# Robot_demoborad.net
KiCad netlist of a schematic drawn in Altium Designer
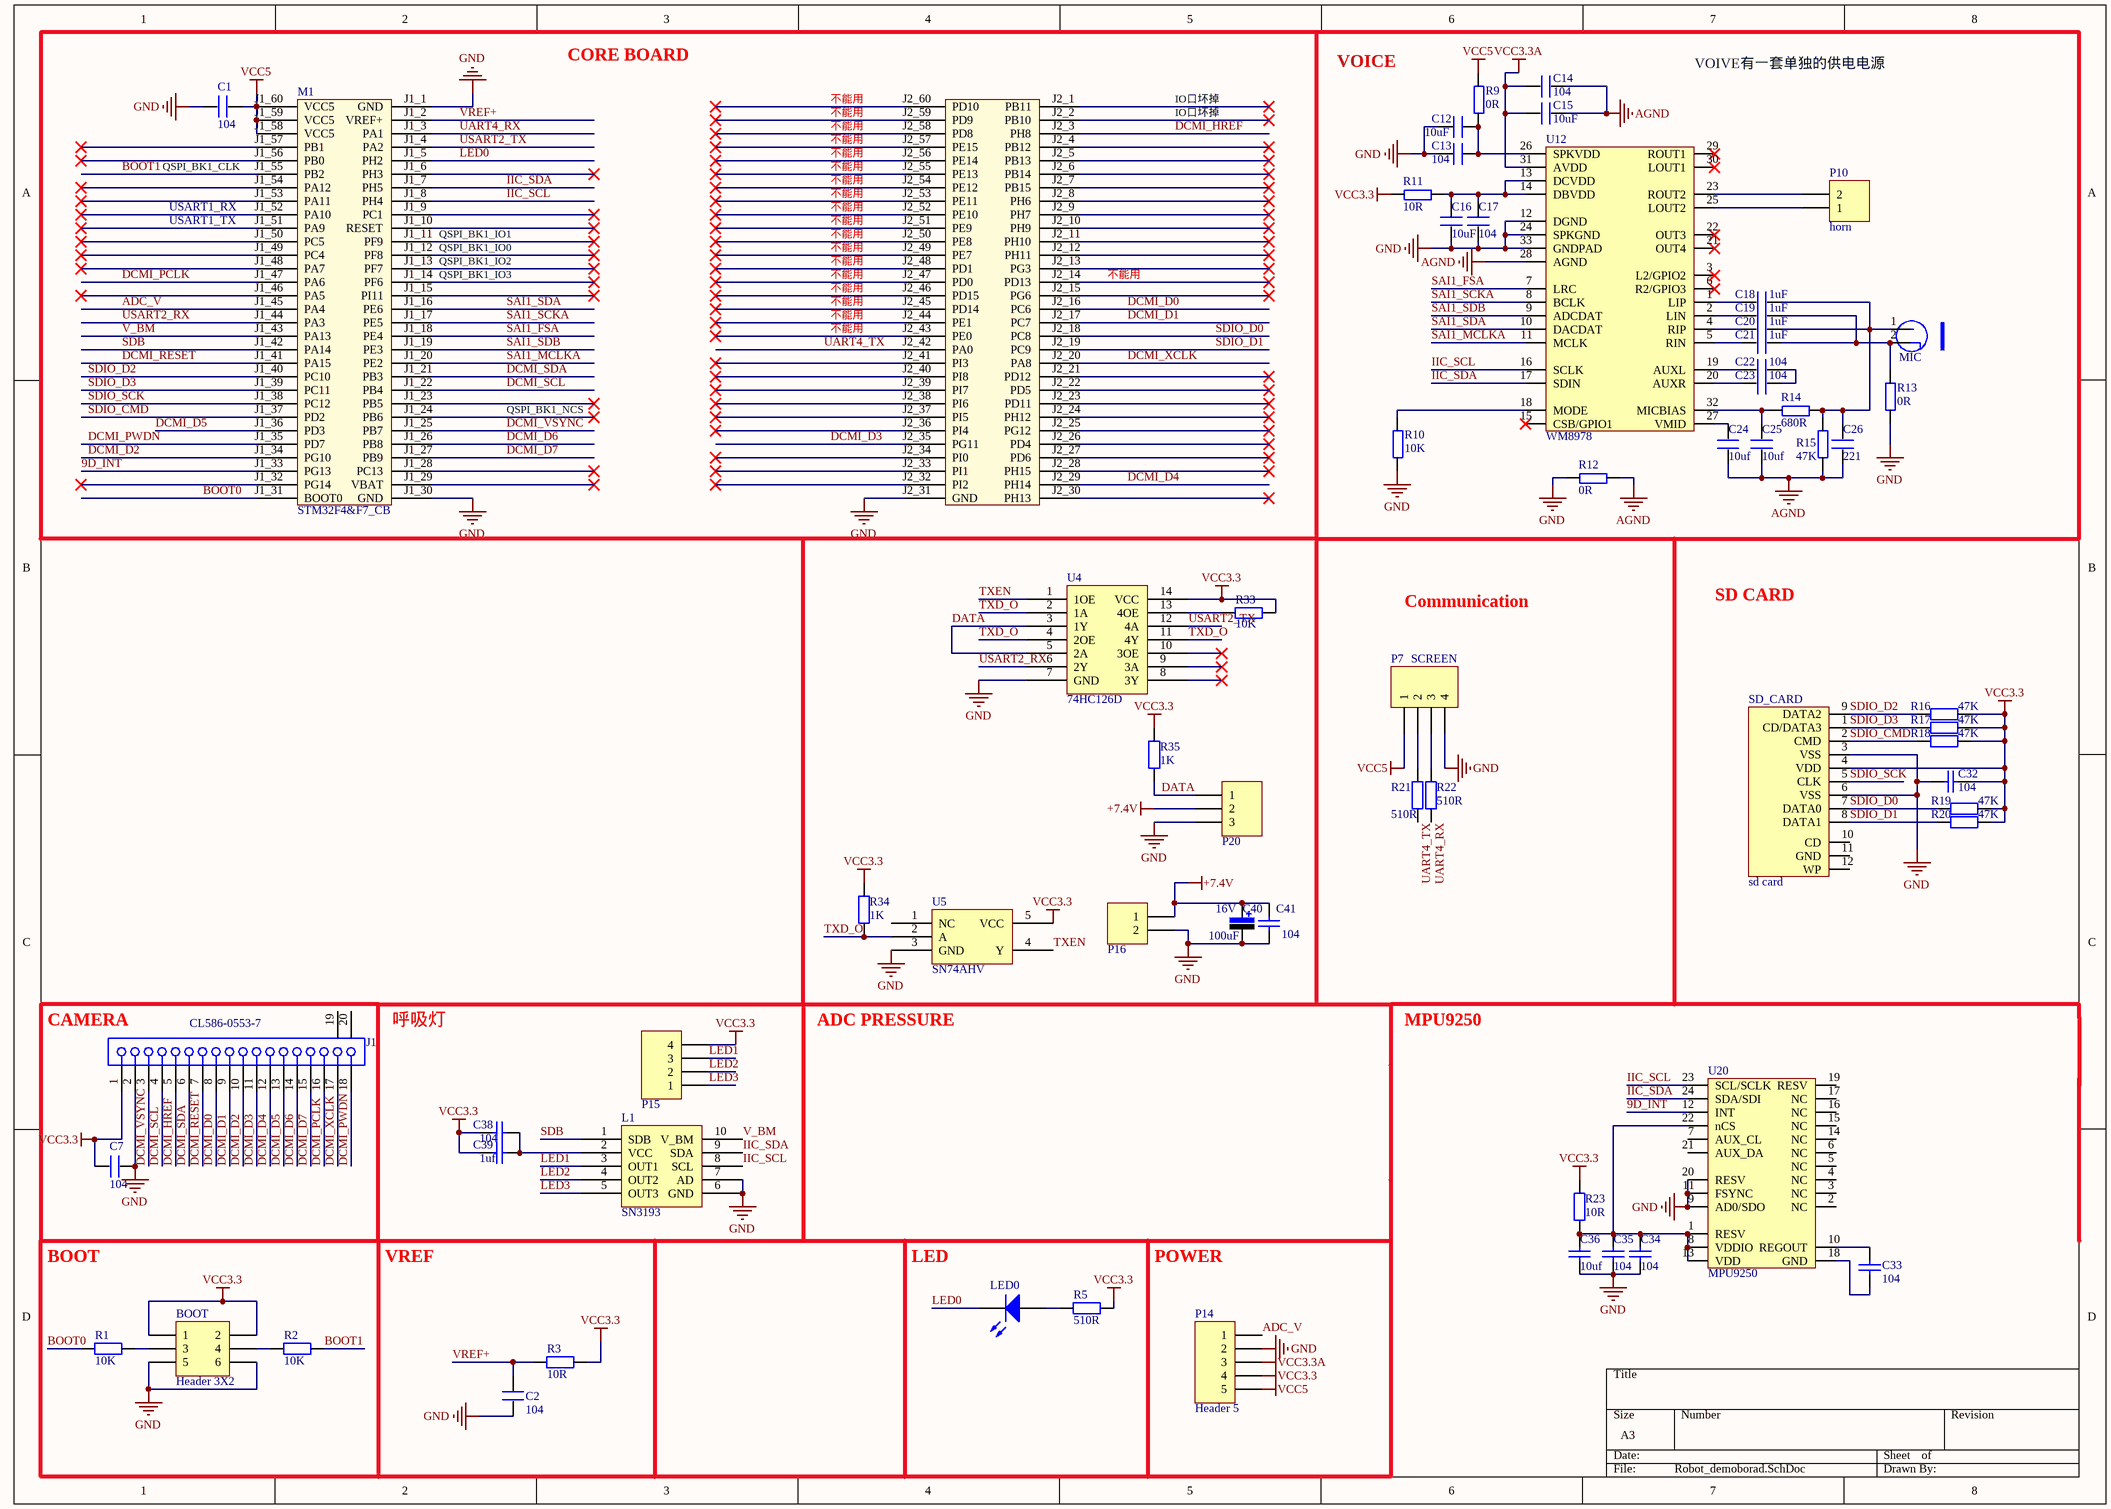
[diagram p0: Robot_demoborad.SchDoc]

(export (version "E")
  (design (tool "Eeschema 10.0.6"))
  (components
    (comp (ref "BOOT")
      (value "Header 3X2")
      (footprint "HDR2X3")
      (description "Header, 3-Pin, Dual row")
      (fields (field (name "PUBLISHER") "Altium Limited"))
      (libsource (lib "阿波罗STM32F4&F7底板封装库") (part "Header 3X2"))
    )
    (comp (ref "C1") (value "104") (footprint "0805") (libsource (lib "阿波罗STM32F4&F7底板封装库") (part "C")))
    (comp (ref "C2") (value "104") (footprint "0805") (libsource (lib "阿波罗STM32F4&F7底板封装库") (part "C")))
    (comp (ref "C7") (value "104") (footprint "0805") (libsource (lib "阿波罗STM32F4&F7底板封装库") (part "C")))
    (comp (ref "C12") (value "10uF") (footprint "0603P") (libsource (lib "阿波罗STM32F4&F7底板封装库") (part "C")))
    (comp (ref "C13") (value "104") (footprint "0603P") (libsource (lib "阿波罗STM32F4&F7底板封装库") (part "C")))
    (comp (ref "C14") (value "104") (footprint "0603P") (libsource (lib "阿波罗STM32F4&F7底板封装库") (part "C")))
    (comp (ref "C15") (value "10uF") (footprint "0603P") (libsource (lib "阿波罗STM32F4&F7底板封装库") (part "C")))
    (comp (ref "C16") (value "10uF") (footprint "0603P") (libsource (lib "阿波罗STM32F4&F7底板封装库") (part "C")))
    (comp (ref "C17") (value "104") (footprint "0603P") (libsource (lib "阿波罗STM32F4&F7底板封装库") (part "C")))
    (comp (ref "C18") (value "1uF") (footprint "0603P") (libsource (lib "阿波罗STM32F4&F7底板封装库") (part "C")))
    (comp (ref "C19") (value "1uF") (footprint "0603P") (libsource (lib "阿波罗STM32F4&F7底板封装库") (part "C")))
    (comp (ref "C20") (value "1uF") (footprint "0603P") (libsource (lib "阿波罗STM32F4&F7底板封装库") (part "C")))
    (comp (ref "C21") (value "1uF") (footprint "0603P") (libsource (lib "阿波罗STM32F4&F7底板封装库") (part "C")))
    (comp (ref "C22") (value "104") (footprint "0603P") (libsource (lib "阿波罗STM32F4&F7底板封装库") (part "C")))
    (comp (ref "C23") (value "104") (footprint "0603P") (libsource (lib "阿波罗STM32F4&F7底板封装库") (part "C")))
    (comp (ref "C24") (value "10uf") (footprint "0603P") (libsource (lib "阿波罗STM32F4&F7底板封装库") (part "C")))
    (comp (ref "C25") (value "10uf") (footprint "0603P") (libsource (lib "阿波罗STM32F4&F7底板封装库") (part "C")))
    (comp (ref "C26") (value "221") (footprint "0603P") (libsource (lib "阿波罗STM32F4&F7底板封装库") (part "C")))
    (comp (ref "C32")
      (value "104")
      (footprint "C-RAD-0805")
      (description "无极性电容")
      (fields (field (name "Comment") "Cap") (field (name "PUBLISHER") "Altium Limited"))
      (libsource (lib "Fszhang") (part "Cap"))
    )
    (comp (ref "C33")
      (value "104")
      (footprint "0603P")
      (description "无极性电容")
      (fields (field (name "Comment") "Cap") (field (name "PUBLISHER") "Altium Limited"))
      (libsource (lib "Fszhang") (part "Cap"))
    )
    (comp (ref "C34")
      (value "104")
      (footprint "0603P")
      (description "无极性电容")
      (fields (field (name "Comment") "Cap") (field (name "PUBLISHER") "Altium Limited"))
      (libsource (lib "Fszhang") (part "Cap"))
    )
    (comp (ref "C35")
      (value "104")
      (footprint "0603P")
      (description "无极性电容")
      (fields (field (name "Comment") "Cap") (field (name "PUBLISHER") "Altium Limited"))
      (libsource (lib "Fszhang") (part "Cap"))
    )
    (comp (ref "C36")
      (value "10uf")
      (footprint "0603P")
      (description "无极性电容")
      (fields (field (name "Comment") "Cap") (field (name "PUBLISHER") "Altium Limited"))
      (libsource (lib "Fszhang") (part "Cap"))
    )
    (comp (ref "C38")
      (value "104")
      (footprint "C-RAD-0805")
      (description "无极性电容")
      (fields (field (name "Comment") "Cap") (field (name "PUBLISHER") "Altium Limited"))
      (libsource (lib "Fszhang") (part "Cap"))
    )
    (comp (ref "C39")
      (value "1uf")
      (footprint "C-RAD-0805")
      (description "无极性电容")
      (fields (field (name "Comment") "Cap") (field (name "PUBLISHER") "Altium Limited"))
      (libsource (lib "Fszhang") (part "Cap"))
    )
    (comp (ref "C40")
      (value "100uF")
      (footprint "C-RB-8")
      (description "极性电解电容")
      (fields
        (field (name "VOL") "16V")
        (field (name "Comment") "Cap Pol")
        (field (name "PUBLISHER") "Altium Limited")
      )
      (libsource (lib "Fszhang") (part "Cap Pol"))
    )
    (comp (ref "C41")
      (value "104")
      (footprint "C-RAD-0805")
      (description "无极性电容")
      (fields (field (name "Comment") "Cap") (field (name "PUBLISHER") "Altium Limited"))
      (libsource (lib "Fszhang") (part "Cap"))
    )
    (comp (ref "J1")
      (value "CL586-0553-7")
      (footprint "FH12A-18S-0.5SH")
      (description "FH12 Series, \"Flip-Lock\" SMT/ZIF Connector - 0.5mm Spaced Top Contact")
      (fields (field (name "PUBLISHER") "Altium Limited"))
      (libsource (lib "HRS FPC-FFC FH12 Series") (part "CL586-0553-7"))
    )
    (comp (ref "L1") (value "SN3193") (footprint "DFN_10") (libsource (lib "SN393") (part "Component_1")))
    (comp (ref "LED0")
      (value "LED1")
      (footprint "6-0805_M")
      (description "Typical RED, GREEN, YELLOW, AMBER GaAs LED")
      (fields (field (name "PUBLISHER") "Altium Limited"))
      (libsource (lib "阿波罗STM32F4&F7底板封装库") (part "LED2"))
    )
    (comp (ref "M1")
      (value "STM32F4&F7_CB")
      (footprint "STM32F4&F7_CB")
      (description "F429/746 Core Board")
      (libsource (lib "阿波罗STM32F4&F7底板封装库") (part "STM32F4&F7_CB"))
    )
    (comp (ref "MIC1")
      (value "MIC")
      (footprint "HDR2X1_B1")
      (libsource (lib "阿波罗STM32F4&F7底板封装库") (part "MIC"))
    )
    (comp (ref "P7")
      (value "SCREEN")
      (footprint "HDR1X4H")
      (description "Header, 4-Pin, Right Angle")
      (fields (field (name "PUBLISHER") "Altium Limited"))
      (libsource (lib "Miscellaneous Connectors") (part "Header 4H"))
    )
    (comp (ref "P10")
      (value "horn")
      (footprint "HDR1X2H")
      (description "Header, 2-Pin, Right Angle")
      (fields (field (name "PUBLISHER") "Altium Limited"))
      (libsource (lib "Miscellaneous Connectors") (part "Header 2H"))
    )
    (comp (ref "P14")
      (value "Header 5")
      (footprint "HDR1X5H")
      (description "Header, 5-Pin")
      (fields (field (name "PUBLISHER") "Altium Limited"))
      (libsource (lib "Miscellaneous Connectors") (part "Header 5"))
    )
    (comp (ref "P15")
      (value "Header 4")
      (footprint "HDR4X1_B2")
      (description "接插件")
      (fields (field (name "PUBLISHER") "Altium Limited"))
      (libsource (lib "Fszhang") (part "Header 4"))
    )
    (comp (ref "P16")
      (value "Header 2")
      (footprint "HDR2X1_B2")
      (description "接插件")
      (fields (field (name "PUBLISHER") "Altium Limited"))
      (libsource (lib "Fszhang") (part "Header 2"))
    )
    (comp (ref "P20")
      (value "Header 3")
      (footprint "HDR3X1_B1")
      (description "接插件")
      (fields (field (name "PUBLISHER") "Altium Limited"))
      (libsource (lib "Fszhang") (part "Header 3"))
    )
    (comp (ref "R1")
      (value "10K")
      (footprint "6-0805_N")
      (description "Resistor")
      (fields (field (name "Comment") "Res2") (field (name "PUBLISHER") "Altium Limited"))
      (libsource (lib "Miscellaneous Devices") (part "Res2"))
    )
    (comp (ref "R2")
      (value "10K")
      (footprint "6-0805_N")
      (description "Resistor")
      (fields (field (name "Comment") "Res2") (field (name "PUBLISHER") "Altium Limited"))
      (libsource (lib "Miscellaneous Devices") (part "Res2"))
    )
    (comp (ref "R3")
      (value "10R")
      (footprint "6-0805_N")
      (description "Resistor")
      (fields (field (name "Comment") "Res2") (field (name "PUBLISHER") "Altium Limited"))
      (libsource (lib "Miscellaneous Devices") (part "Res2"))
    )
    (comp (ref "R5")
      (value "510R")
      (footprint "6-0805_N")
      (description "Resistor")
      (fields (field (name "Comment") "Res2") (field (name "PUBLISHER") "Altium Limited"))
      (libsource (lib "Miscellaneous Devices") (part "Res2"))
    )
    (comp (ref "R9") (value "0R") (footprint "0603P") (libsource (lib "阿波罗STM32F4&F7底板封装库") (part "R")))
    (comp (ref "R10") (value "10K") (footprint "0603P") (libsource (lib "阿波罗STM32F4&F7底板封装库") (part "R")))
    (comp (ref "R11") (value "10R") (footprint "0603P") (libsource (lib "阿波罗STM32F4&F7底板封装库") (part "R")))
    (comp (ref "R12") (value "0R") (footprint "0603P") (libsource (lib "阿波罗STM32F4&F7底板封装库") (part "R")))
    (comp (ref "R13") (value "0R") (footprint "0603P") (libsource (lib "阿波罗STM32F4&F7底板封装库") (part "R")))
    (comp (ref "R14") (value "680R") (footprint "0603P") (libsource (lib "阿波罗STM32F4&F7底板封装库") (part "R")))
    (comp (ref "R15") (value "47K") (footprint "0603P") (libsource (lib "阿波罗STM32F4&F7底板封装库") (part "R")))
    (comp (ref "R16")
      (value "47K")
      (footprint "0805-1")
      (description "贴片电阻")
      (fields (field (name "Comment") "Res1") (field (name "PUBLISHER") "Altium Limited"))
      (libsource (lib "") (part "Res1_1"))
    )
    (comp (ref "R17")
      (value "47K")
      (footprint "0805-1")
      (description "贴片电阻")
      (fields (field (name "Comment") "Res1") (field (name "PUBLISHER") "Altium Limited"))
      (libsource (lib "") (part "Res1_1"))
    )
    (comp (ref "R18")
      (value "47K")
      (footprint "0805-1")
      (description "贴片电阻")
      (fields (field (name "Comment") "Res1") (field (name "PUBLISHER") "Altium Limited"))
      (libsource (lib "") (part "Res1_1"))
    )
    (comp (ref "R19")
      (value "47K")
      (footprint "0805-1")
      (description "贴片电阻")
      (fields (field (name "Comment") "Res1") (field (name "PUBLISHER") "Altium Limited"))
      (libsource (lib "") (part "Res1_1"))
    )
    (comp (ref "R20")
      (value "47K")
      (footprint "0805-1")
      (description "贴片电阻")
      (fields (field (name "Comment") "Res1") (field (name "PUBLISHER") "Altium Limited"))
      (libsource (lib "") (part "Res1_1"))
    )
    (comp (ref "R21")
      (value "510R")
      (footprint "0805-1")
      (description "贴片电阻")
      (fields (field (name "Comment") "Res1") (field (name "PUBLISHER") "Altium Limited"))
      (libsource (lib "Fszhang") (part "Res1"))
    )
    (comp (ref "R22")
      (value "510R")
      (footprint "0805-1")
      (description "贴片电阻")
      (fields (field (name "Comment") "Res1") (field (name "PUBLISHER") "Altium Limited"))
      (libsource (lib "Fszhang") (part "Res1"))
    )
    (comp (ref "R23")
      (value "10R")
      (footprint "0603P")
      (description "贴片电阻")
      (fields (field (name "Comment") "Res1") (field (name "PUBLISHER") "Altium Limited"))
      (libsource (lib "Fszhang") (part "Res1"))
    )
    (comp (ref "R33")
      (value "10K")
      (footprint "0805-1")
      (description "贴片电阻")
      (fields (field (name "Comment") "Res1") (field (name "PUBLISHER") "Altium Limited"))
      (libsource (lib "") (part "Res1_1"))
    )
    (comp (ref "R34")
      (value "1K")
      (footprint "0805-1")
      (description "贴片电阻")
      (fields (field (name "Comment") "Res1") (field (name "PUBLISHER") "Altium Limited"))
      (libsource (lib "Fszhang") (part "Res1"))
    )
    (comp (ref "R35")
      (value "1K")
      (footprint "0805-1")
      (description "贴片电阻")
      (fields (field (name "Comment") "Res1") (field (name "PUBLISHER") "Altium Limited"))
      (libsource (lib "Fszhang") (part "Res1"))
    )
    (comp (ref "SD_CARD")
      (value "sd card")
      (footprint "SDCARD_L")
      (libsource (lib "阿波罗STM32F4&F7底板封装库") (part "sd card"))
    )
    (comp (ref "U4")
      (value "74HC126D")
      (footprint "SOP-14N")
      (libsource (lib "74HC126D") (part "Component_1"))
    )
    (comp (ref "U5")
      (value "SN74AHV")
      (footprint "SOT-23-5")
      (libsource (lib "SN74AHV") (part "Component_1"))
    )
    (comp (ref "U12")
      (value "WM8978")
      (footprint "qfn32")
      (description "24bit ADC&DAC")
      (libsource (lib "阿波罗STM32F4&F7底板封装库") (part "WM8978"))
    )
    (comp (ref "U20")
      (value "MPU9250")
      (footprint "QFN24-t")
      (description "9轴运动处理传感器")
      (libsource (lib "阿波罗STM32F4&F7底板封装库") (part "MPU9250"))
    )
  )
  (nets
    (net (code "1") (name "+7.4V") (class "Default")
      (node (ref "C40") (pin "1") (pinfunction "1_1") (pintype "passive"))
      (node (ref "C41") (pin "2") (pinfunction "2_2") (pintype "passive"))
      (node (ref "P16") (pin "1") (pinfunction "1_1") (pintype "passive"))
      (node (ref "P20") (pin "2") (pinfunction "2_2") (pintype "passive"))
    )
    (net (code "2") (name "/9D_INT") (class "Default")
      (node (ref "M1") (pin "J1_33") (pinfunction "PG13_J1_33") (pintype "passive"))
      (node (ref "U20") (pin "12") (pinfunction "INT_12") (pintype "passive"))
    )
    (net (code "3") (name "/ADC_V") (class "Default")
      (node (ref "M1") (pin "J1_45") (pinfunction "PA4_J1_45") (pintype "passive"))
      (node (ref "P14") (pin "1") (pinfunction "1_1") (pintype "passive"))
    )
    (net (code "4") (name "/BOOT0") (class "Default")
      (node (ref "M1") (pin "J1_31") (pinfunction "BOOT0_J1_31") (pintype "passive"))
      (node (ref "R1") (pin "1") (pinfunction "1_1") (pintype "passive"))
    )
    (net (code "5") (name "/BOOT1") (class "Default")
      (node (ref "M1") (pin "J1_55") (pinfunction "PB2_J1_55") (pintype "passive"))
      (node (ref "R2") (pin "2") (pinfunction "2_2") (pintype "passive"))
    )
    (net (code "6") (name "/DATA") (class "Default")
      (node (ref "P20") (pin "1") (pinfunction "1_1") (pintype "passive"))
      (node (ref "R35") (pin "1") (pinfunction "1_1") (pintype "passive"))
      (node (ref "U4") (pin "3") (pinfunction "1Y_3") (pintype "passive"))
      (node (ref "U4") (pin "5") (pinfunction "2A_5") (pintype "passive"))
    )
    (net (code "7") (name "/DCMI_D0") (class "Default")
      (node (ref "J1") (pin "8") (pinfunction "8_8") (pintype "passive"))
      (node (ref "M1") (pin "J2_16") (pinfunction "PC6_J2_16") (pintype "passive"))
    )
    (net (code "8") (name "/DCMI_D1") (class "Default")
      (node (ref "J1") (pin "9") (pinfunction "9_9") (pintype "passive"))
      (node (ref "M1") (pin "J2_17") (pinfunction "PC7_J2_17") (pintype "passive"))
    )
    (net (code "9") (name "/DCMI_D2") (class "Default")
      (node (ref "J1") (pin "10") (pinfunction "10_10") (pintype "passive"))
      (node (ref "M1") (pin "J1_34") (pinfunction "PG10_J1_34") (pintype "passive"))
    )
    (net (code "10") (name "/DCMI_D3") (class "Default")
      (node (ref "J1") (pin "11") (pinfunction "11_11") (pintype "passive"))
      (node (ref "M1") (pin "J2_35") (pinfunction "PG11_J2_35") (pintype "passive"))
    )
    (net (code "11") (name "/DCMI_D4") (class "Default")
      (node (ref "J1") (pin "12") (pinfunction "12_12") (pintype "passive"))
      (node (ref "M1") (pin "J2_29") (pinfunction "PH14_J2_29") (pintype "passive"))
    )
    (net (code "12") (name "/DCMI_D5") (class "Default")
      (node (ref "J1") (pin "13") (pinfunction "13_13") (pintype "passive"))
      (node (ref "M1") (pin "J1_36") (pinfunction "PD3_J1_36") (pintype "passive"))
    )
    (net (code "13") (name "/DCMI_D6") (class "Default")
      (node (ref "J1") (pin "14") (pinfunction "14_14") (pintype "passive"))
      (node (ref "M1") (pin "J1_26") (pinfunction "PB8_J1_26") (pintype "passive"))
    )
    (net (code "14") (name "/DCMI_D7") (class "Default")
      (node (ref "J1") (pin "15") (pinfunction "15_15") (pintype "passive"))
      (node (ref "M1") (pin "J1_27") (pinfunction "PB9_J1_27") (pintype "passive"))
    )
    (net (code "15") (name "/DCMI_HREF") (class "Default")
      (node (ref "J1") (pin "5") (pinfunction "5_5") (pintype "passive"))
      (node (ref "M1") (pin "J2_3") (pinfunction "PH8_J2_3") (pintype "passive"))
    )
    (net (code "16") (name "/DCMI_PCLK") (class "Default")
      (node (ref "J1") (pin "16") (pinfunction "16_16") (pintype "passive"))
      (node (ref "M1") (pin "J1_47") (pinfunction "PA6_J1_47") (pintype "passive"))
    )
    (net (code "17") (name "/DCMI_PWDN") (class "Default")
      (node (ref "J1") (pin "18") (pinfunction "18_18") (pintype "passive"))
      (node (ref "M1") (pin "J1_35") (pinfunction "PD7_J1_35") (pintype "passive"))
    )
    (net (code "18") (name "/DCMI_RESET") (class "Default")
      (node (ref "J1") (pin "7") (pinfunction "7_7") (pintype "passive"))
      (node (ref "M1") (pin "J1_41") (pinfunction "PA15_J1_41") (pintype "passive"))
    )
    (net (code "19") (name "/DCMI_SCL") (class "Default")
      (node (ref "J1") (pin "4") (pinfunction "4_4") (pintype "passive"))
      (node (ref "M1") (pin "J1_22") (pinfunction "PB4_J1_22") (pintype "passive"))
    )
    (net (code "20") (name "/DCMI_SDA") (class "Default")
      (node (ref "J1") (pin "6") (pinfunction "6_6") (pintype "passive"))
      (node (ref "M1") (pin "J1_21") (pinfunction "PB3_J1_21") (pintype "passive"))
    )
    (net (code "21") (name "/DCMI_VSYNC") (class "Default")
      (node (ref "J1") (pin "3") (pinfunction "3_3") (pintype "passive"))
      (node (ref "M1") (pin "J1_25") (pinfunction "PB7_J1_25") (pintype "passive"))
    )
    (net (code "22") (name "/DCMI_XCLK") (class "Default")
      (node (ref "J1") (pin "17") (pinfunction "17_17") (pintype "passive"))
      (node (ref "M1") (pin "J2_20") (pinfunction "PA8_J2_20") (pintype "passive"))
    )
    (net (code "23") (name "/IIC_SCL") (class "Default")
      (node (ref "L1") (pin "8") (pinfunction "SCL_8") (pintype "passive"))
      (node (ref "M1") (pin "J1_8") (pinfunction "PH4_J1_8") (pintype "passive"))
      (node (ref "U12") (pin "16") (pinfunction "SCLK_16") (pintype "passive"))
      (node (ref "U20") (pin "23") (pinfunction "SCL/SCLK_23") (pintype "passive"))
    )
    (net (code "24") (name "/IIC_SDA") (class "Default")
      (node (ref "L1") (pin "9") (pinfunction "SDA_9") (pintype "passive"))
      (node (ref "M1") (pin "J1_7") (pinfunction "PH5_J1_7") (pintype "passive"))
      (node (ref "U12") (pin "17") (pinfunction "SDIN_17") (pintype "passive"))
      (node (ref "U20") (pin "24") (pinfunction "SDA/SDI_24") (pintype "passive"))
    )
    (net (code "25") (name "/LED0") (class "Default")
      (node (ref "LED0") (pin "2") (pinfunction "K_2") (pintype "passive"))
      (node (ref "M1") (pin "J1_5") (pinfunction "PH2_J1_5") (pintype "passive"))
    )
    (net (code "26") (name "/LED1") (class "Default")
      (node (ref "L1") (pin "3") (pinfunction "OUT1_3") (pintype "passive"))
      (node (ref "P15") (pin "3") (pinfunction "3_3") (pintype "passive"))
    )
    (net (code "27") (name "/LED2") (class "Default")
      (node (ref "L1") (pin "4") (pinfunction "OUT2_4") (pintype "passive"))
      (node (ref "P15") (pin "2") (pinfunction "2_2") (pintype "passive"))
    )
    (net (code "28") (name "/LED3") (class "Default")
      (node (ref "L1") (pin "5") (pinfunction "OUT3_5") (pintype "passive"))
      (node (ref "P15") (pin "1") (pinfunction "1_1") (pintype "passive"))
    )
    (net (code "29") (name "/SAI1_FSA") (class "Default")
      (node (ref "M1") (pin "J1_18") (pinfunction "PE4_J1_18") (pintype "passive"))
      (node (ref "U12") (pin "7") (pinfunction "LRC_7") (pintype "passive"))
    )
    (net (code "30") (name "/SAI1_MCLKA") (class "Default")
      (node (ref "M1") (pin "J1_20") (pinfunction "PE2_J1_20") (pintype "passive"))
      (node (ref "U12") (pin "11") (pinfunction "MCLK_11") (pintype "passive"))
    )
    (net (code "31") (name "/SAI1_SCKA") (class "Default")
      (node (ref "M1") (pin "J1_17") (pinfunction "PE5_J1_17") (pintype "passive"))
      (node (ref "U12") (pin "8") (pinfunction "BCLK_8") (pintype "passive"))
    )
    (net (code "32") (name "/SAI1_SDA") (class "Default")
      (node (ref "M1") (pin "J1_16") (pinfunction "PE6_J1_16") (pintype "passive"))
      (node (ref "U12") (pin "10") (pinfunction "DACDAT_10") (pintype "passive"))
    )
    (net (code "33") (name "/SAI1_SDB") (class "Default")
      (node (ref "M1") (pin "J1_19") (pinfunction "PE3_J1_19") (pintype "passive"))
      (node (ref "U12") (pin "9") (pinfunction "ADCDAT_9") (pintype "passive"))
    )
    (net (code "34") (name "/SDB") (class "Default")
      (node (ref "L1") (pin "1") (pinfunction "SDB_1") (pintype "passive"))
      (node (ref "M1") (pin "J1_42") (pinfunction "PA14_J1_42") (pintype "passive"))
    )
    (net (code "35") (name "/SDIO_CMD") (class "Default")
      (node (ref "M1") (pin "J1_37") (pinfunction "PD2_J1_37") (pintype "passive"))
      (node (ref "R18") (pin "1") (pinfunction "1_1") (pintype "passive"))
      (node (ref "SD_CARD") (pin "2") (pinfunction "CMD_2") (pintype "passive"))
    )
    (net (code "36") (name "/SDIO_D0") (class "Default")
      (node (ref "M1") (pin "J2_18") (pinfunction "PC8_J2_18") (pintype "passive"))
      (node (ref "R19") (pin "1") (pinfunction "1_1") (pintype "passive"))
      (node (ref "SD_CARD") (pin "7") (pinfunction "DATA0_7") (pintype "passive"))
    )
    (net (code "37") (name "/SDIO_D1") (class "Default")
      (node (ref "M1") (pin "J2_19") (pinfunction "PC9_J2_19") (pintype "passive"))
      (node (ref "R20") (pin "1") (pinfunction "1_1") (pintype "passive"))
      (node (ref "SD_CARD") (pin "8") (pinfunction "DATA1_8") (pintype "passive"))
    )
    (net (code "38") (name "/SDIO_D2") (class "Default")
      (node (ref "M1") (pin "J1_40") (pinfunction "PC10_J1_40") (pintype "passive"))
      (node (ref "R16") (pin "1") (pinfunction "1_1") (pintype "passive"))
      (node (ref "SD_CARD") (pin "9") (pinfunction "DATA2_9") (pintype "passive"))
    )
    (net (code "39") (name "/SDIO_D3") (class "Default")
      (node (ref "M1") (pin "J1_39") (pinfunction "PC11_J1_39") (pintype "passive"))
      (node (ref "R17") (pin "1") (pinfunction "1_1") (pintype "passive"))
      (node (ref "SD_CARD") (pin "1") (pinfunction "CD/DATA3_1") (pintype "passive"))
    )
    (net (code "40") (name "/SDIO_SCK") (class "Default")
      (node (ref "M1") (pin "J1_38") (pinfunction "PC12_J1_38") (pintype "passive"))
      (node (ref "SD_CARD") (pin "5") (pinfunction "CLK_5") (pintype "passive"))
    )
    (net (code "41") (name "/TXD_O") (class "Default")
      (node (ref "R34") (pin "1") (pinfunction "1_1") (pintype "passive"))
      (node (ref "U4") (pin "11") (pinfunction "4Y_11") (pintype "passive"))
      (node (ref "U4") (pin "2") (pinfunction "1A_2") (pintype "passive"))
      (node (ref "U4") (pin "4") (pinfunction "2OE_4") (pintype "passive"))
      (node (ref "U5") (pin "2") (pinfunction "A_2") (pintype "passive"))
    )
    (net (code "42") (name "/TXEN") (class "Default")
      (node (ref "U4") (pin "1") (pinfunction "1OE_1") (pintype "passive"))
      (node (ref "U5") (pin "4") (pinfunction "Y_4") (pintype "passive"))
    )
    (net (code "43") (name "/UART4_RX") (class "Default")
      (node (ref "M1") (pin "J1_3") (pinfunction "PA1_J1_3") (pintype "passive"))
      (node (ref "R22") (pin "1") (pinfunction "1_1") (pintype "passive"))
    )
    (net (code "44") (name "/UART4_TX") (class "Default")
      (node (ref "M1") (pin "J2_42") (pinfunction "PA0_J2_42") (pintype "passive"))
      (node (ref "R21") (pin "1") (pinfunction "1_1") (pintype "passive"))
    )
    (net (code "45") (name "/USART2_RX") (class "Default")
      (node (ref "M1") (pin "J1_44") (pinfunction "PA3_J1_44") (pintype "passive"))
      (node (ref "U4") (pin "6") (pinfunction "2Y_6") (pintype "passive"))
    )
    (net (code "46") (name "/USART2_TX") (class "Default")
      (node (ref "M1") (pin "J1_4") (pinfunction "PA2_J1_4") (pintype "passive"))
      (node (ref "U4") (pin "12") (pinfunction "4A_12") (pintype "passive"))
    )
    (net (code "47") (name "/VREF+") (class "Default")
      (node (ref "C2") (pin "2") (pintype "passive"))
      (node (ref "M1") (pin "J1_2") (pinfunction "VREF+_J1_2") (pintype "passive"))
      (node (ref "R3") (pin "1") (pinfunction "1_1") (pintype "passive"))
    )
    (net (code "48") (name "/V_BM") (class "Default")
      (node (ref "L1") (pin "10") (pinfunction "V_BM_10") (pintype "passive"))
      (node (ref "M1") (pin "J1_43") (pinfunction "PA13_J1_43") (pintype "passive"))
    )
    (net (code "49") (name "AGND") (class "Default")
      (node (ref "C14") (pin "2") (pintype "passive"))
      (node (ref "C15") (pin "2") (pintype "passive"))
      (node (ref "C24") (pin "1") (pintype "passive"))
      (node (ref "C25") (pin "1") (pintype "passive"))
      (node (ref "C26") (pin "1") (pintype "passive"))
      (node (ref "R12") (pin "2") (pintype "passive"))
      (node (ref "R15") (pin "1") (pintype "passive"))
      (node (ref "U12") (pin "28") (pinfunction "AGND_28") (pintype "passive"))
    )
    (net (code "50") (name "GND") (class "Default")
      (node (ref "BOOT") (pin "5") (pinfunction "5_5") (pintype "passive"))
      (node (ref "BOOT") (pin "6") (pinfunction "6_6") (pintype "passive"))
      (node (ref "C1") (pin "1") (pintype "passive"))
      (node (ref "C12") (pin "1") (pintype "passive"))
      (node (ref "C13") (pin "1") (pintype "passive"))
      (node (ref "C16") (pin "1") (pintype "passive"))
      (node (ref "C17") (pin "1") (pintype "passive"))
      (node (ref "C2") (pin "1") (pintype "passive"))
      (node (ref "C32") (pin "1") (pinfunction "1_1") (pintype "passive"))
      (node (ref "C34") (pin "1") (pinfunction "1_1") (pintype "passive"))
      (node (ref "C35") (pin "1") (pinfunction "1_1") (pintype "passive"))
      (node (ref "C36") (pin "1") (pinfunction "1_1") (pintype "passive"))
      (node (ref "C40") (pin "2") (pinfunction "2_2") (pintype "passive"))
      (node (ref "C41") (pin "1") (pinfunction "1_1") (pintype "passive"))
      (node (ref "C7") (pin "2") (pintype "passive"))
      (node (ref "J1") (pin "2") (pinfunction "2_2") (pintype "passive"))
      (node (ref "L1") (pin "6") (pinfunction "GND_6") (pintype "passive"))
      (node (ref "L1") (pin "7") (pinfunction "AD_7") (pintype "passive"))
      (node (ref "M1") (pin "J1_1") (pinfunction "GND_J1_1") (pintype "passive"))
      (node (ref "M1") (pin "J1_30") (pinfunction "GND_J1_30") (pintype "passive"))
      (node (ref "M1") (pin "J2_31") (pinfunction "GND_J2_31") (pintype "passive"))
      (node (ref "P14") (pin "2") (pinfunction "2_2") (pintype "passive"))
      (node (ref "P16") (pin "2") (pinfunction "2_2") (pintype "passive"))
      (node (ref "P20") (pin "3") (pinfunction "3_3") (pintype "passive"))
      (node (ref "P7") (pin "4") (pinfunction "4_4") (pintype "passive"))
      (node (ref "R10") (pin "1") (pintype "passive"))
      (node (ref "R12") (pin "1") (pintype "passive"))
      (node (ref "R13") (pin "1") (pintype "passive"))
      (node (ref "SD_CARD") (pin "3") (pinfunction "VSS_3") (pintype "passive"))
      (node (ref "SD_CARD") (pin "6") (pinfunction "VSS_6") (pintype "passive"))
      (node (ref "U12") (pin "12") (pinfunction "DGND_12") (pintype "passive"))
      (node (ref "U12") (pin "24") (pinfunction "SPKGND_24") (pintype "passive"))
      (node (ref "U12") (pin "33") (pinfunction "GNDPAD_33") (pintype "passive"))
      (node (ref "U20") (pin "11") (pinfunction "FSYNC_11") (pintype "passive"))
      (node (ref "U20") (pin "20") (pinfunction "RESV_20") (pintype "passive"))
      (node (ref "U20") (pin "9") (pinfunction "AD0/SDO_9") (pintype "passive"))
      (node (ref "U4") (pin "7") (pinfunction "GND_7") (pintype "passive"))
      (node (ref "U5") (pin "3") (pinfunction "GND_3") (pintype "passive"))
    )
    (net (code "51") (name "Net-(BOOT-Pad3)") (class "Default")
      (node (ref "BOOT") (pin "3") (pinfunction "3_3") (pintype "passive"))
      (node (ref "R1") (pin "2") (pinfunction "2_2") (pintype "passive"))
    )
    (net (code "52") (name "Net-(BOOT-Pad4)") (class "Default")
      (node (ref "BOOT") (pin "4") (pinfunction "4_4") (pintype "passive"))
      (node (ref "R2") (pin "1") (pinfunction "1_1") (pintype "passive"))
    )
    (net (code "53") (name "Net-(C22-Pad2)") (class "Default")
      (node (ref "C22") (pin "2") (pintype "passive"))
      (node (ref "C23") (pin "2") (pintype "passive"))
    )
    (net (code "54") (name "Net-(L1-VCC)") (class "Default")
      (node (ref "C38") (pin "2") (pinfunction "2_2") (pintype "passive"))
      (node (ref "C39") (pin "2") (pinfunction "2_2") (pintype "passive"))
      (node (ref "L1") (pin "2") (pinfunction "VCC_2") (pintype "passive"))
    )
    (net (code "55") (name "Net-(LED0-A)") (class "Default")
      (node (ref "LED0") (pin "1") (pinfunction "A_1") (pintype "passive"))
      (node (ref "R5") (pin "1") (pinfunction "1_1") (pintype "passive"))
    )
    (net (code "56") (name "Net-(MIC1-GND)") (class "Default")
      (node (ref "C19") (pin "2") (pintype "passive"))
      (node (ref "C21") (pin "2") (pintype "passive"))
      (node (ref "MIC1") (pin "2") (pinfunction "GND_2") (pintype "passive"))
      (node (ref "R13") (pin "2") (pintype "passive"))
    )
    (net (code "57") (name "Net-(MIC1-VCC)") (class "Default")
      (node (ref "C18") (pin "2") (pintype "passive"))
      (node (ref "C20") (pin "2") (pintype "passive"))
      (node (ref "C26") (pin "2") (pintype "passive"))
      (node (ref "MIC1") (pin "1") (pinfunction "VCC_1") (pintype "passive"))
      (node (ref "R14") (pin "2") (pintype "passive"))
      (node (ref "R15") (pin "2") (pintype "passive"))
    )
    (net (code "58") (name "Net-(P7-Pad2)") (class "Default")
      (node (ref "P7") (pin "2") (pinfunction "2_2") (pintype "passive"))
      (node (ref "R21") (pin "2") (pinfunction "2_2") (pintype "passive"))
    )
    (net (code "59") (name "Net-(P7-Pad3)") (class "Default")
      (node (ref "P7") (pin "3") (pinfunction "3_3") (pintype "passive"))
      (node (ref "R22") (pin "2") (pinfunction "2_2") (pintype "passive"))
    )
    (net (code "60") (name "Net-(U4-4OE)") (class "Default")
      (node (ref "R33") (pin "1") (pinfunction "1_1") (pintype "passive"))
      (node (ref "U4") (pin "13") (pinfunction "4OE_13") (pintype "passive"))
    )
    (net (code "61") (name "Net-(U12-AUXL)") (class "Default")
      (node (ref "C22") (pin "1") (pintype "passive"))
      (node (ref "U12") (pin "19") (pinfunction "AUXL_19") (pintype "passive"))
    )
    (net (code "62") (name "Net-(U12-AUXR)") (class "Default")
      (node (ref "C23") (pin "1") (pintype "passive"))
      (node (ref "U12") (pin "20") (pinfunction "AUXR_20") (pintype "passive"))
    )
    (net (code "63") (name "Net-(U12-DBVDD)") (class "Default")
      (node (ref "C16") (pin "2") (pintype "passive"))
      (node (ref "C17") (pin "2") (pintype "passive"))
      (node (ref "R11") (pin "2") (pintype "passive"))
      (node (ref "U12") (pin "13") (pinfunction "DCVDD_13") (pintype "passive"))
      (node (ref "U12") (pin "14") (pinfunction "DBVDD_14") (pintype "passive"))
    )
    (net (code "64") (name "Net-(U12-LIN)") (class "Default")
      (node (ref "C19") (pin "1") (pintype "passive"))
      (node (ref "U12") (pin "2") (pinfunction "LIN_2") (pintype "passive"))
    )
    (net (code "65") (name "Net-(U12-LIP)") (class "Default")
      (node (ref "C18") (pin "1") (pintype "passive"))
      (node (ref "U12") (pin "1") (pinfunction "LIP_1") (pintype "passive"))
    )
    (net (code "66") (name "Net-(U12-LOUT2)") (class "Default")
      (node (ref "P10") (pin "1") (pinfunction "1_1") (pintype "passive"))
      (node (ref "U12") (pin "25") (pinfunction "LOUT2_25") (pintype "passive"))
    )
    (net (code "67") (name "Net-(U12-MICBIAS)") (class "Default")
      (node (ref "C25") (pin "2") (pintype "passive"))
      (node (ref "R14") (pin "1") (pintype "passive"))
      (node (ref "U12") (pin "32") (pinfunction "MICBIAS_32") (pintype "passive"))
    )
    (net (code "68") (name "Net-(U12-MODE)") (class "Default")
      (node (ref "R10") (pin "2") (pintype "passive"))
      (node (ref "U12") (pin "18") (pinfunction "MODE_18") (pintype "passive"))
    )
    (net (code "69") (name "Net-(U12-RIN)") (class "Default")
      (node (ref "C21") (pin "1") (pintype "passive"))
      (node (ref "U12") (pin "5") (pinfunction "RIN_5") (pintype "passive"))
    )
    (net (code "70") (name "Net-(U12-RIP)") (class "Default")
      (node (ref "C20") (pin "1") (pintype "passive"))
      (node (ref "U12") (pin "4") (pinfunction "RIP_4") (pintype "passive"))
    )
    (net (code "71") (name "Net-(U12-ROUT2)") (class "Default")
      (node (ref "P10") (pin "2") (pinfunction "2_2") (pintype "passive"))
      (node (ref "U12") (pin "23") (pinfunction "ROUT2_23") (pintype "passive"))
    )
    (net (code "72") (name "Net-(U12-SPKVDD)") (class "Default")
      (node (ref "C12") (pin "2") (pintype "passive"))
      (node (ref "C13") (pin "2") (pintype "passive"))
      (node (ref "R9") (pin "1") (pintype "passive"))
      (node (ref "U12") (pin "26") (pinfunction "SPKVDD_26") (pintype "passive"))
    )
    (net (code "73") (name "Net-(U12-VMID)") (class "Default")
      (node (ref "C24") (pin "2") (pintype "passive"))
      (node (ref "U12") (pin "27") (pinfunction "VMID_27") (pintype "passive"))
    )
    (net (code "74") (name "Net-(U20-GND)") (class "Default")
      (node (ref "C33") (pin "1") (pinfunction "1_1") (pintype "passive"))
      (node (ref "U20") (pin "18") (pinfunction "GND_18") (pintype "passive"))
    )
    (net (code "75") (name "Net-(U20-REGOUT)") (class "Default")
      (node (ref "C33") (pin "2") (pinfunction "2_2") (pintype "passive"))
      (node (ref "U20") (pin "10") (pinfunction "REGOUT_10") (pintype "passive"))
    )
    (net (code "76") (name "Net-(U20-VDD)") (class "Default")
      (node (ref "C34") (pin "2") (pinfunction "2_2") (pintype "passive"))
      (node (ref "C35") (pin "2") (pinfunction "2_2") (pintype "passive"))
      (node (ref "C36") (pin "2") (pinfunction "2_2") (pintype "passive"))
      (node (ref "R23") (pin "1") (pinfunction "1_1") (pintype "passive"))
      (node (ref "U20") (pin "1") (pinfunction "RESV_1") (pintype "passive"))
      (node (ref "U20") (pin "13") (pinfunction "VDD_13") (pintype "passive"))
      (node (ref "U20") (pin "22") (pinfunction "nCS_22") (pintype "passive"))
      (node (ref "U20") (pin "8") (pinfunction "VDDIO_8") (pintype "passive"))
    )
    (net (code "77") (name "VCC3.3") (class "Default")
      (node (ref "BOOT") (pin "1") (pinfunction "1_1") (pintype "passive"))
      (node (ref "BOOT") (pin "2") (pinfunction "2_2") (pintype "passive"))
      (node (ref "C32") (pin "2") (pinfunction "2_2") (pintype "passive"))
      (node (ref "C38") (pin "1") (pinfunction "1_1") (pintype "passive"))
      (node (ref "C39") (pin "1") (pinfunction "1_1") (pintype "passive"))
      (node (ref "C7") (pin "1") (pintype "passive"))
      (node (ref "J1") (pin "1") (pinfunction "1_1") (pintype "passive"))
      (node (ref "P14") (pin "4") (pinfunction "4_4") (pintype "passive"))
      (node (ref "P15") (pin "4") (pinfunction "4_4") (pintype "passive"))
      (node (ref "R11") (pin "1") (pintype "passive"))
      (node (ref "R16") (pin "2") (pinfunction "2_2") (pintype "passive"))
      (node (ref "R17") (pin "2") (pinfunction "2_2") (pintype "passive"))
      (node (ref "R18") (pin "2") (pinfunction "2_2") (pintype "passive"))
      (node (ref "R19") (pin "2") (pinfunction "2_2") (pintype "passive"))
      (node (ref "R20") (pin "2") (pinfunction "2_2") (pintype "passive"))
      (node (ref "R23") (pin "2") (pinfunction "2_2") (pintype "passive"))
      (node (ref "R3") (pin "2") (pinfunction "2_2") (pintype "passive"))
      (node (ref "R33") (pin "2") (pinfunction "2_2") (pintype "passive"))
      (node (ref "R34") (pin "2") (pinfunction "2_2") (pintype "passive"))
      (node (ref "R35") (pin "2") (pinfunction "2_2") (pintype "passive"))
      (node (ref "R5") (pin "2") (pinfunction "2_2") (pintype "passive"))
      (node (ref "SD_CARD") (pin "4") (pinfunction "VDD_4") (pintype "passive"))
      (node (ref "U4") (pin "14") (pinfunction "VCC_14") (pintype "passive"))
      (node (ref "U5") (pin "5") (pinfunction "VCC_5") (pintype "passive"))
    )
    (net (code "78") (name "VCC3.3A") (class "Default")
      (node (ref "C14") (pin "1") (pintype "passive"))
      (node (ref "C15") (pin "1") (pintype "passive"))
      (node (ref "P14") (pin "3") (pinfunction "3_3") (pintype "passive"))
      (node (ref "U12") (pin "31") (pinfunction "AVDD_31") (pintype "passive"))
    )
    (net (code "79") (name "VCC5") (class "Default")
      (node (ref "C1") (pin "2") (pintype "passive"))
      (node (ref "M1") (pin "J1_58") (pinfunction "VCC5_J1_58") (pintype "passive"))
      (node (ref "M1") (pin "J1_59") (pinfunction "VCC5_J1_59") (pintype "passive"))
      (node (ref "M1") (pin "J1_60") (pinfunction "VCC5_J1_60") (pintype "passive"))
      (node (ref "P14") (pin "5") (pinfunction "5_5") (pintype "passive"))
      (node (ref "P7") (pin "1") (pinfunction "1_1") (pintype "passive"))
      (node (ref "R9") (pin "2") (pintype "passive"))
    )
    (net (code "80") (name "unconnected-(J1-MH1-Pad19)") (class "Default")
      (node (ref "J1") (pin "19") (pinfunction "MH1_19") (pintype "passive"))
    )
    (net (code "81") (name "unconnected-(J1-MH2-Pad20)") (class "Default")
      (node (ref "J1") (pin "20") (pinfunction "MH2_20") (pintype "passive"))
    )
    (net (code "82") (name "unconnected-(M1-PA5-PadJ1_46)") (class "Default")
      (node (ref "M1") (pin "J1_46") (pinfunction "PA5_J1_46") (pintype "passive+no_connect"))
    )
    (net (code "83") (name "unconnected-(M1-PA7-PadJ1_48)") (class "Default")
      (node (ref "M1") (pin "J1_48") (pinfunction "PA7_J1_48") (pintype "passive+no_connect"))
    )
    (net (code "84") (name "unconnected-(M1-PA9-PadJ1_51)") (class "Default")
      (node (ref "M1") (pin "J1_51") (pinfunction "PA9_J1_51") (pintype "passive+no_connect"))
    )
    (net (code "85") (name "unconnected-(M1-PA10-PadJ1_52)") (class "Default")
      (node (ref "M1") (pin "J1_52") (pinfunction "PA10_J1_52") (pintype "passive+no_connect"))
    )
    (net (code "86") (name "unconnected-(M1-PA11-PadJ1_53)") (class "Default")
      (node (ref "M1") (pin "J1_53") (pinfunction "PA11_J1_53") (pintype "passive+no_connect"))
    )
    (net (code "87") (name "unconnected-(M1-PA12-PadJ1_54)") (class "Default")
      (node (ref "M1") (pin "J1_54") (pinfunction "PA12_J1_54") (pintype "passive+no_connect"))
    )
    (net (code "88") (name "unconnected-(M1-PB0-PadJ1_56)") (class "Default")
      (node (ref "M1") (pin "J1_56") (pinfunction "PB0_J1_56") (pintype "passive+no_connect"))
    )
    (net (code "89") (name "unconnected-(M1-PB1-PadJ1_57)") (class "Default")
      (node (ref "M1") (pin "J1_57") (pinfunction "PB1_J1_57") (pintype "passive+no_connect"))
    )
    (net (code "90") (name "unconnected-(M1-PB5-PadJ1_23)") (class "Default")
      (node (ref "M1") (pin "J1_23") (pinfunction "PB5_J1_23") (pintype "passive+no_connect"))
    )
    (net (code "91") (name "unconnected-(M1-PB6-PadJ1_24)") (class "Default")
      (node (ref "M1") (pin "J1_24") (pinfunction "PB6_J1_24") (pintype "passive+no_connect"))
    )
    (net (code "92") (name "unconnected-(M1-PB10-PadJ2_2)") (class "Default")
      (node (ref "M1") (pin "J2_2") (pinfunction "PB10_J2_2") (pintype "passive+no_connect"))
    )
    (net (code "93") (name "unconnected-(M1-PB11-PadJ2_1)") (class "Default")
      (node (ref "M1") (pin "J2_1") (pinfunction "PB11_J2_1") (pintype "passive+no_connect"))
    )
    (net (code "94") (name "unconnected-(M1-PB12-PadJ2_4)") (class "Default")
      (node (ref "M1") (pin "J2_4") (pinfunction "PB12_J2_4") (pintype "passive+no_connect"))
    )
    (net (code "95") (name "unconnected-(M1-PB13-PadJ2_5)") (class "Default")
      (node (ref "M1") (pin "J2_5") (pinfunction "PB13_J2_5") (pintype "passive+no_connect"))
    )
    (net (code "96") (name "unconnected-(M1-PB14-PadJ2_6)") (class "Default")
      (node (ref "M1") (pin "J2_6") (pinfunction "PB14_J2_6") (pintype "passive+no_connect"))
    )
    (net (code "97") (name "unconnected-(M1-PB15-PadJ2_7)") (class "Default")
      (node (ref "M1") (pin "J2_7") (pinfunction "PB15_J2_7") (pintype "passive+no_connect"))
    )
    (net (code "98") (name "unconnected-(M1-PC1-PadJ1_9)") (class "Default")
      (node (ref "M1") (pin "J1_9") (pinfunction "PC1_J1_9") (pintype "passive+no_connect"))
    )
    (net (code "99") (name "unconnected-(M1-PC4-PadJ1_49)") (class "Default")
      (node (ref "M1") (pin "J1_49") (pinfunction "PC4_J1_49") (pintype "passive+no_connect"))
    )
    (net (code "100") (name "unconnected-(M1-PC5-PadJ1_50)") (class "Default")
      (node (ref "M1") (pin "J1_50") (pinfunction "PC5_J1_50") (pintype "passive+no_connect"))
    )
    (net (code "101") (name "unconnected-(M1-PC13-PadJ1_28)") (class "Default")
      (node (ref "M1") (pin "J1_28") (pinfunction "PC13_J1_28") (pintype "passive+no_connect"))
    )
    (net (code "102") (name "unconnected-(M1-PD0-PadJ2_47)") (class "Default")
      (node (ref "M1") (pin "J2_47") (pinfunction "PD0_J2_47") (pintype "passive+no_connect"))
    )
    (net (code "103") (name "unconnected-(M1-PD1-PadJ2_48)") (class "Default")
      (node (ref "M1") (pin "J2_48") (pinfunction "PD1_J2_48") (pintype "passive+no_connect"))
    )
    (net (code "104") (name "unconnected-(M1-PD4-PadJ2_26)") (class "Default")
      (node (ref "M1") (pin "J2_26") (pinfunction "PD4_J2_26") (pintype "passive+no_connect"))
    )
    (net (code "105") (name "unconnected-(M1-PD5-PadJ2_22)") (class "Default")
      (node (ref "M1") (pin "J2_22") (pinfunction "PD5_J2_22") (pintype "passive+no_connect"))
    )
    (net (code "106") (name "unconnected-(M1-PD6-PadJ2_27)") (class "Default")
      (node (ref "M1") (pin "J2_27") (pinfunction "PD6_J2_27") (pintype "passive+no_connect"))
    )
    (net (code "107") (name "unconnected-(M1-PD8-PadJ2_58)") (class "Default")
      (node (ref "M1") (pin "J2_58") (pinfunction "PD8_J2_58") (pintype "passive+no_connect"))
    )
    (net (code "108") (name "unconnected-(M1-PD9-PadJ2_59)") (class "Default")
      (node (ref "M1") (pin "J2_59") (pinfunction "PD9_J2_59") (pintype "passive+no_connect"))
    )
    (net (code "109") (name "unconnected-(M1-PD10-PadJ2_60)") (class "Default")
      (node (ref "M1") (pin "J2_60") (pinfunction "PD10_J2_60") (pintype "passive+no_connect"))
    )
    (net (code "110") (name "unconnected-(M1-PD11-PadJ2_23)") (class "Default")
      (node (ref "M1") (pin "J2_23") (pinfunction "PD11_J2_23") (pintype "passive+no_connect"))
    )
    (net (code "111") (name "unconnected-(M1-PD12-PadJ2_21)") (class "Default")
      (node (ref "M1") (pin "J2_21") (pinfunction "PD12_J2_21") (pintype "passive+no_connect"))
    )
    (net (code "112") (name "unconnected-(M1-PD13-PadJ2_14)") (class "Default")
      (node (ref "M1") (pin "J2_14") (pinfunction "PD13_J2_14") (pintype "passive+no_connect"))
    )
    (net (code "113") (name "unconnected-(M1-PD14-PadJ2_45)") (class "Default")
      (node (ref "M1") (pin "J2_45") (pinfunction "PD14_J2_45") (pintype "passive+no_connect"))
    )
    (net (code "114") (name "unconnected-(M1-PD15-PadJ2_46)") (class "Default")
      (node (ref "M1") (pin "J2_46") (pinfunction "PD15_J2_46") (pintype "passive+no_connect"))
    )
    (net (code "115") (name "unconnected-(M1-PE0-PadJ2_43)") (class "Default")
      (node (ref "M1") (pin "J2_43") (pinfunction "PE0_J2_43") (pintype "passive+no_connect"))
    )
    (net (code "116") (name "unconnected-(M1-PE1-PadJ2_44)") (class "Default")
      (node (ref "M1") (pin "J2_44") (pinfunction "PE1_J2_44") (pintype "passive+no_connect"))
    )
    (net (code "117") (name "unconnected-(M1-PE7-PadJ2_49)") (class "Default")
      (node (ref "M1") (pin "J2_49") (pinfunction "PE7_J2_49") (pintype "passive+no_connect"))
    )
    (net (code "118") (name "unconnected-(M1-PE8-PadJ2_50)") (class "Default")
      (node (ref "M1") (pin "J2_50") (pinfunction "PE8_J2_50") (pintype "passive+no_connect"))
    )
    (net (code "119") (name "unconnected-(M1-PE9-PadJ2_51)") (class "Default")
      (node (ref "M1") (pin "J2_51") (pinfunction "PE9_J2_51") (pintype "passive+no_connect"))
    )
    (net (code "120") (name "unconnected-(M1-PE10-PadJ2_52)") (class "Default")
      (node (ref "M1") (pin "J2_52") (pinfunction "PE10_J2_52") (pintype "passive+no_connect"))
    )
    (net (code "121") (name "unconnected-(M1-PE11-PadJ2_53)") (class "Default")
      (node (ref "M1") (pin "J2_53") (pinfunction "PE11_J2_53") (pintype "passive+no_connect"))
    )
    (net (code "122") (name "unconnected-(M1-PE12-PadJ2_54)") (class "Default")
      (node (ref "M1") (pin "J2_54") (pinfunction "PE12_J2_54") (pintype "passive+no_connect"))
    )
    (net (code "123") (name "unconnected-(M1-PE13-PadJ2_55)") (class "Default")
      (node (ref "M1") (pin "J2_55") (pinfunction "PE13_J2_55") (pintype "passive+no_connect"))
    )
    (net (code "124") (name "unconnected-(M1-PE14-PadJ2_56)") (class "Default")
      (node (ref "M1") (pin "J2_56") (pinfunction "PE14_J2_56") (pintype "passive+no_connect"))
    )
    (net (code "125") (name "unconnected-(M1-PE15-PadJ2_57)") (class "Default")
      (node (ref "M1") (pin "J2_57") (pinfunction "PE15_J2_57") (pintype "passive+no_connect"))
    )
    (net (code "126") (name "unconnected-(M1-PF6-PadJ1_14)") (class "Default")
      (node (ref "M1") (pin "J1_14") (pinfunction "PF6_J1_14") (pintype "passive+no_connect"))
    )
    (net (code "127") (name "unconnected-(M1-PF7-PadJ1_13)") (class "Default")
      (node (ref "M1") (pin "J1_13") (pinfunction "PF7_J1_13") (pintype "passive+no_connect"))
    )
    (net (code "128") (name "unconnected-(M1-PF8-PadJ1_12)") (class "Default")
      (node (ref "M1") (pin "J1_12") (pinfunction "PF8_J1_12") (pintype "passive+no_connect"))
    )
    (net (code "129") (name "unconnected-(M1-PF9-PadJ1_11)") (class "Default")
      (node (ref "M1") (pin "J1_11") (pinfunction "PF9_J1_11") (pintype "passive+no_connect"))
    )
    (net (code "130") (name "unconnected-(M1-PG3-PadJ2_13)") (class "Default")
      (node (ref "M1") (pin "J2_13") (pinfunction "PG3_J2_13") (pintype "passive+no_connect"))
    )
    (net (code "131") (name "unconnected-(M1-PG6-PadJ2_15)") (class "Default")
      (node (ref "M1") (pin "J2_15") (pinfunction "PG6_J2_15") (pintype "passive+no_connect"))
    )
    (net (code "132") (name "unconnected-(M1-PG12-PadJ2_25)") (class "Default")
      (node (ref "M1") (pin "J2_25") (pinfunction "PG12_J2_25") (pintype "passive+no_connect"))
    )
    (net (code "133") (name "unconnected-(M1-PG14-PadJ1_32)") (class "Default")
      (node (ref "M1") (pin "J1_32") (pinfunction "PG14_J1_32") (pintype "passive+no_connect"))
    )
    (net (code "134") (name "unconnected-(M1-PH3-PadJ1_6)") (class "Default")
      (node (ref "M1") (pin "J1_6") (pinfunction "PH3_J1_6") (pintype "passive+no_connect"))
    )
    (net (code "135") (name "unconnected-(M1-PH6-PadJ2_8)") (class "Default")
      (node (ref "M1") (pin "J2_8") (pinfunction "PH6_J2_8") (pintype "passive+no_connect"))
    )
    (net (code "136") (name "unconnected-(M1-PH7-PadJ2_9)") (class "Default")
      (node (ref "M1") (pin "J2_9") (pinfunction "PH7_J2_9") (pintype "passive+no_connect"))
    )
    (net (code "137") (name "unconnected-(M1-PH9-PadJ2_10)") (class "Default")
      (node (ref "M1") (pin "J2_10") (pinfunction "PH9_J2_10") (pintype "passive+no_connect"))
    )
    (net (code "138") (name "unconnected-(M1-PH10-PadJ2_11)") (class "Default")
      (node (ref "M1") (pin "J2_11") (pinfunction "PH10_J2_11") (pintype "passive+no_connect"))
    )
    (net (code "139") (name "unconnected-(M1-PH11-PadJ2_12)") (class "Default")
      (node (ref "M1") (pin "J2_12") (pinfunction "PH11_J2_12") (pintype "passive+no_connect"))
    )
    (net (code "140") (name "unconnected-(M1-PH12-PadJ2_24)") (class "Default")
      (node (ref "M1") (pin "J2_24") (pinfunction "PH12_J2_24") (pintype "passive+no_connect"))
    )
    (net (code "141") (name "unconnected-(M1-PH13-PadJ2_30)") (class "Default")
      (node (ref "M1") (pin "J2_30") (pinfunction "PH13_J2_30") (pintype "passive+no_connect"))
    )
    (net (code "142") (name "unconnected-(M1-PH15-PadJ2_28)") (class "Default")
      (node (ref "M1") (pin "J2_28") (pinfunction "PH15_J2_28") (pintype "passive+no_connect"))
    )
    (net (code "143") (name "unconnected-(M1-PI0-PadJ2_34)") (class "Default")
      (node (ref "M1") (pin "J2_34") (pinfunction "PI0_J2_34") (pintype "passive+no_connect"))
    )
    (net (code "144") (name "unconnected-(M1-PI1-PadJ2_33)") (class "Default")
      (node (ref "M1") (pin "J2_33") (pinfunction "PI1_J2_33") (pintype "passive+no_connect"))
    )
    (net (code "145") (name "unconnected-(M1-PI2-PadJ2_32)") (class "Default")
      (node (ref "M1") (pin "J2_32") (pinfunction "PI2_J2_32") (pintype "passive+no_connect"))
    )
    (net (code "146") (name "unconnected-(M1-PI3-PadJ2_41)") (class "Default")
      (node (ref "M1") (pin "J2_41") (pinfunction "PI3_J2_41") (pintype "passive+no_connect"))
    )
    (net (code "147") (name "unconnected-(M1-PI4-PadJ2_36)") (class "Default")
      (node (ref "M1") (pin "J2_36") (pinfunction "PI4_J2_36") (pintype "passive+no_connect"))
    )
    (net (code "148") (name "unconnected-(M1-PI5-PadJ2_37)") (class "Default")
      (node (ref "M1") (pin "J2_37") (pinfunction "PI5_J2_37") (pintype "passive+no_connect"))
    )
    (net (code "149") (name "unconnected-(M1-PI6-PadJ2_38)") (class "Default")
      (node (ref "M1") (pin "J2_38") (pinfunction "PI6_J2_38") (pintype "passive+no_connect"))
    )
    (net (code "150") (name "unconnected-(M1-PI7-PadJ2_39)") (class "Default")
      (node (ref "M1") (pin "J2_39") (pinfunction "PI7_J2_39") (pintype "passive+no_connect"))
    )
    (net (code "151") (name "unconnected-(M1-PI8-PadJ2_40)") (class "Default")
      (node (ref "M1") (pin "J2_40") (pinfunction "PI8_J2_40") (pintype "passive+no_connect"))
    )
    (net (code "152") (name "unconnected-(M1-PI11-PadJ1_15)") (class "Default")
      (node (ref "M1") (pin "J1_15") (pinfunction "PI11_J1_15") (pintype "passive+no_connect"))
    )
    (net (code "153") (name "unconnected-(M1-RESET-PadJ1_10)") (class "Default")
      (node (ref "M1") (pin "J1_10") (pinfunction "RESET_J1_10") (pintype "passive+no_connect"))
    )
    (net (code "154") (name "unconnected-(M1-VBAT-PadJ1_29)") (class "Default")
      (node (ref "M1") (pin "J1_29") (pinfunction "VBAT_J1_29") (pintype "passive+no_connect"))
    )
    (net (code "155") (name "unconnected-(SD_CARD-CD-Pad10)") (class "Default")
      (node (ref "SD_CARD") (pin "10") (pinfunction "CD_10") (pintype "passive"))
    )
    (net (code "156") (name "unconnected-(SD_CARD-GND-Pad11)") (class "Default")
      (node (ref "SD_CARD") (pin "11") (pinfunction "GND_11") (pintype "passive"))
    )
    (net (code "157") (name "unconnected-(SD_CARD-WP-Pad12)") (class "Default")
      (node (ref "SD_CARD") (pin "12") (pinfunction "WP_12") (pintype "passive"))
    )
    (net (code "158") (name "unconnected-(U4-3A-Pad9)") (class "Default")
      (node (ref "U4") (pin "9") (pinfunction "3A_9") (pintype "passive+no_connect"))
    )
    (net (code "159") (name "unconnected-(U4-3OE-Pad10)") (class "Default")
      (node (ref "U4") (pin "10") (pinfunction "3OE_10") (pintype "passive+no_connect"))
    )
    (net (code "160") (name "unconnected-(U4-3Y-Pad8)") (class "Default")
      (node (ref "U4") (pin "8") (pinfunction "3Y_8") (pintype "passive+no_connect"))
    )
    (net (code "161") (name "unconnected-(U5-NC-Pad1)") (class "Default")
      (node (ref "U5") (pin "1") (pinfunction "NC_1") (pintype "passive"))
    )
    (net (code "162") (name "unconnected-(U12-CSB{slash}GPIO1-Pad15)") (class "Default")
      (node (ref "U12") (pin "15") (pinfunction "CSB/GPIO1_15") (pintype "passive+no_connect"))
    )
    (net (code "163") (name "unconnected-(U12-L2{slash}GPIO2-Pad3)") (class "Default")
      (node (ref "U12") (pin "3") (pinfunction "L2/GPIO2_3") (pintype "passive+no_connect"))
    )
    (net (code "164") (name "unconnected-(U12-LOUT1-Pad30)") (class "Default")
      (node (ref "U12") (pin "30") (pinfunction "LOUT1_30") (pintype "passive+no_connect"))
    )
    (net (code "165") (name "unconnected-(U12-OUT3-Pad22)") (class "Default")
      (node (ref "U12") (pin "22") (pinfunction "OUT3_22") (pintype "passive+no_connect"))
    )
    (net (code "166") (name "unconnected-(U12-OUT4-Pad21)") (class "Default")
      (node (ref "U12") (pin "21") (pinfunction "OUT4_21") (pintype "passive+no_connect"))
    )
    (net (code "167") (name "unconnected-(U12-R2{slash}GPIO3-Pad6)") (class "Default")
      (node (ref "U12") (pin "6") (pinfunction "R2/GPIO3_6") (pintype "passive+no_connect"))
    )
    (net (code "168") (name "unconnected-(U12-ROUT1-Pad29)") (class "Default")
      (node (ref "U12") (pin "29") (pinfunction "ROUT1_29") (pintype "passive+no_connect"))
    )
    (net (code "169") (name "unconnected-(U20-AUX_CL-Pad7)") (class "Default")
      (node (ref "U20") (pin "7") (pinfunction "AUX_CL_7") (pintype "passive"))
    )
    (net (code "170") (name "unconnected-(U20-AUX_DA-Pad21)") (class "Default")
      (node (ref "U20") (pin "21") (pinfunction "AUX_DA_21") (pintype "passive"))
    )
    (net (code "171") (name "unconnected-(U20-NC-Pad2)") (class "Default")
      (node (ref "U20") (pin "2") (pinfunction "NC_2") (pintype "passive"))
    )
    (net (code "172") (name "unconnected-(U20-NC-Pad3)") (class "Default")
      (node (ref "U20") (pin "3") (pinfunction "NC_3") (pintype "passive"))
    )
    (net (code "173") (name "unconnected-(U20-NC-Pad4)") (class "Default")
      (node (ref "U20") (pin "4") (pinfunction "NC_4") (pintype "passive"))
    )
    (net (code "174") (name "unconnected-(U20-NC-Pad5)") (class "Default")
      (node (ref "U20") (pin "5") (pinfunction "NC_5") (pintype "passive"))
    )
    (net (code "175") (name "unconnected-(U20-NC-Pad6)") (class "Default")
      (node (ref "U20") (pin "6") (pinfunction "NC_6") (pintype "passive"))
    )
    (net (code "176") (name "unconnected-(U20-NC-Pad14)") (class "Default")
      (node (ref "U20") (pin "14") (pinfunction "NC_14") (pintype "passive"))
    )
    (net (code "177") (name "unconnected-(U20-NC-Pad15)") (class "Default")
      (node (ref "U20") (pin "15") (pinfunction "NC_15") (pintype "passive"))
    )
    (net (code "178") (name "unconnected-(U20-NC-Pad16)") (class "Default")
      (node (ref "U20") (pin "16") (pinfunction "NC_16") (pintype "passive"))
    )
    (net (code "179") (name "unconnected-(U20-NC-Pad17)") (class "Default")
      (node (ref "U20") (pin "17") (pinfunction "NC_17") (pintype "passive"))
    )
    (net (code "180") (name "unconnected-(U20-RESV-Pad19)") (class "Default")
      (node (ref "U20") (pin "19") (pinfunction "RESV_19") (pintype "passive"))
    )
  )
)
